# design.net
KiCad netlist of a schematic drawn in Altium Designer
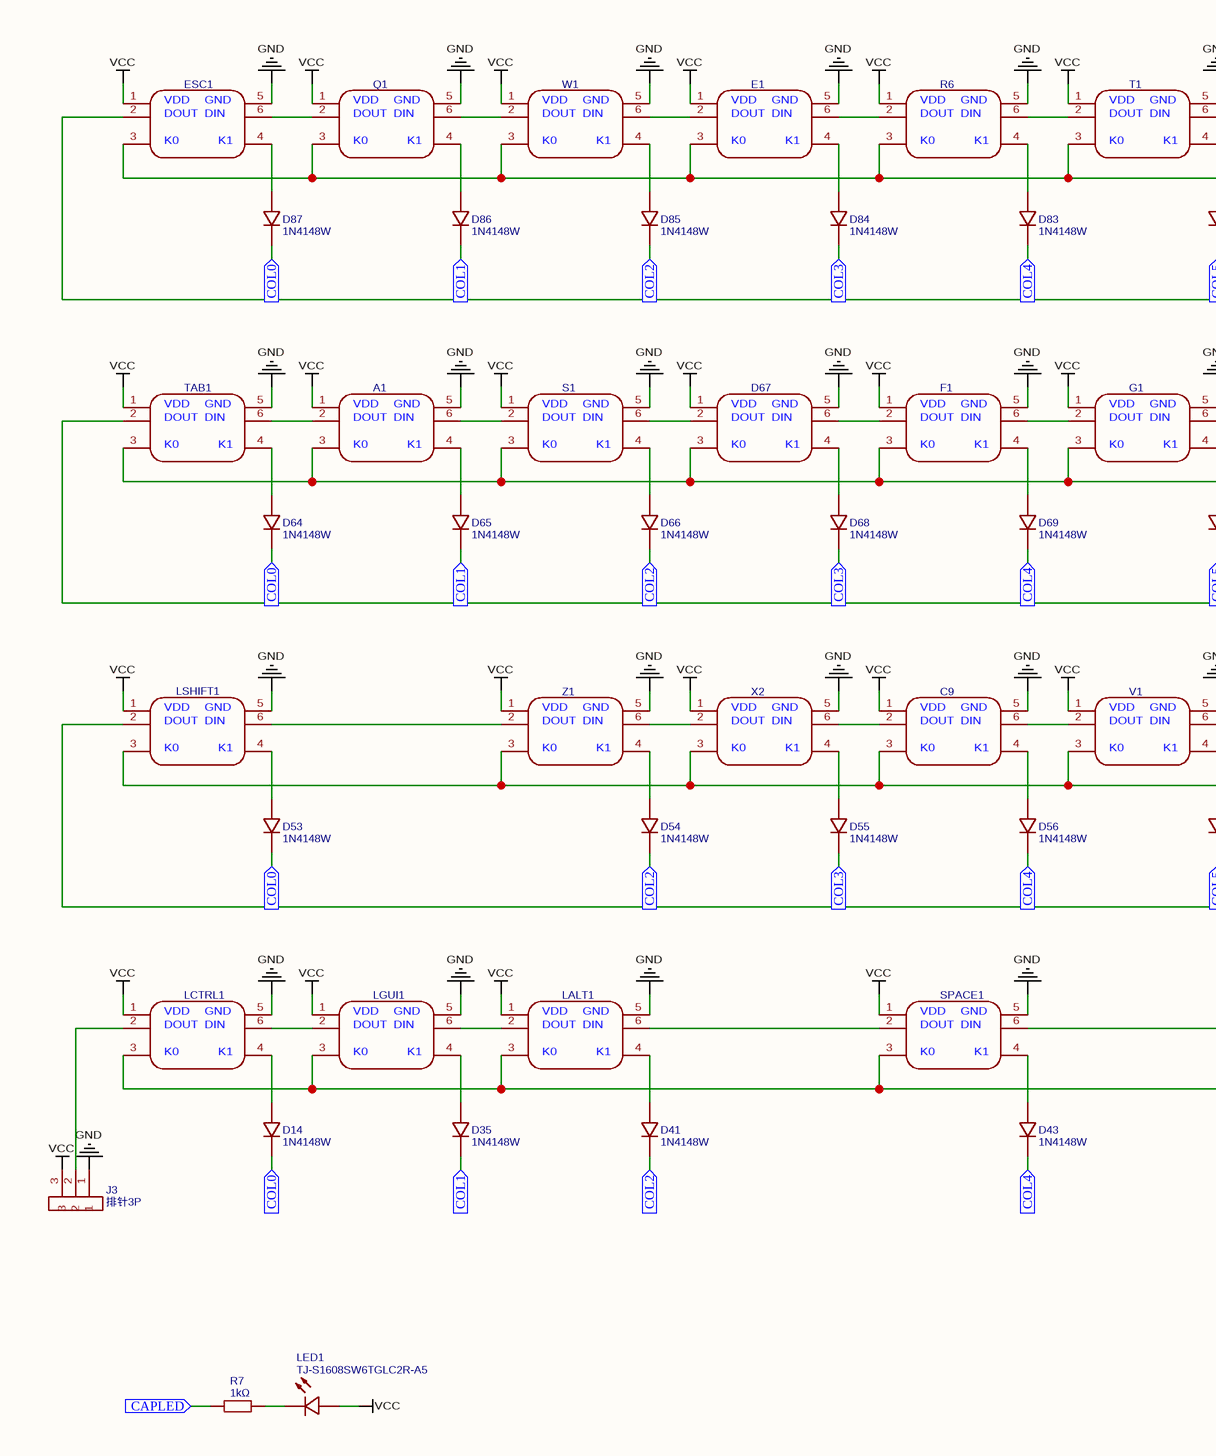
[diagram p0: 键盘矩阵.schdoc, left]
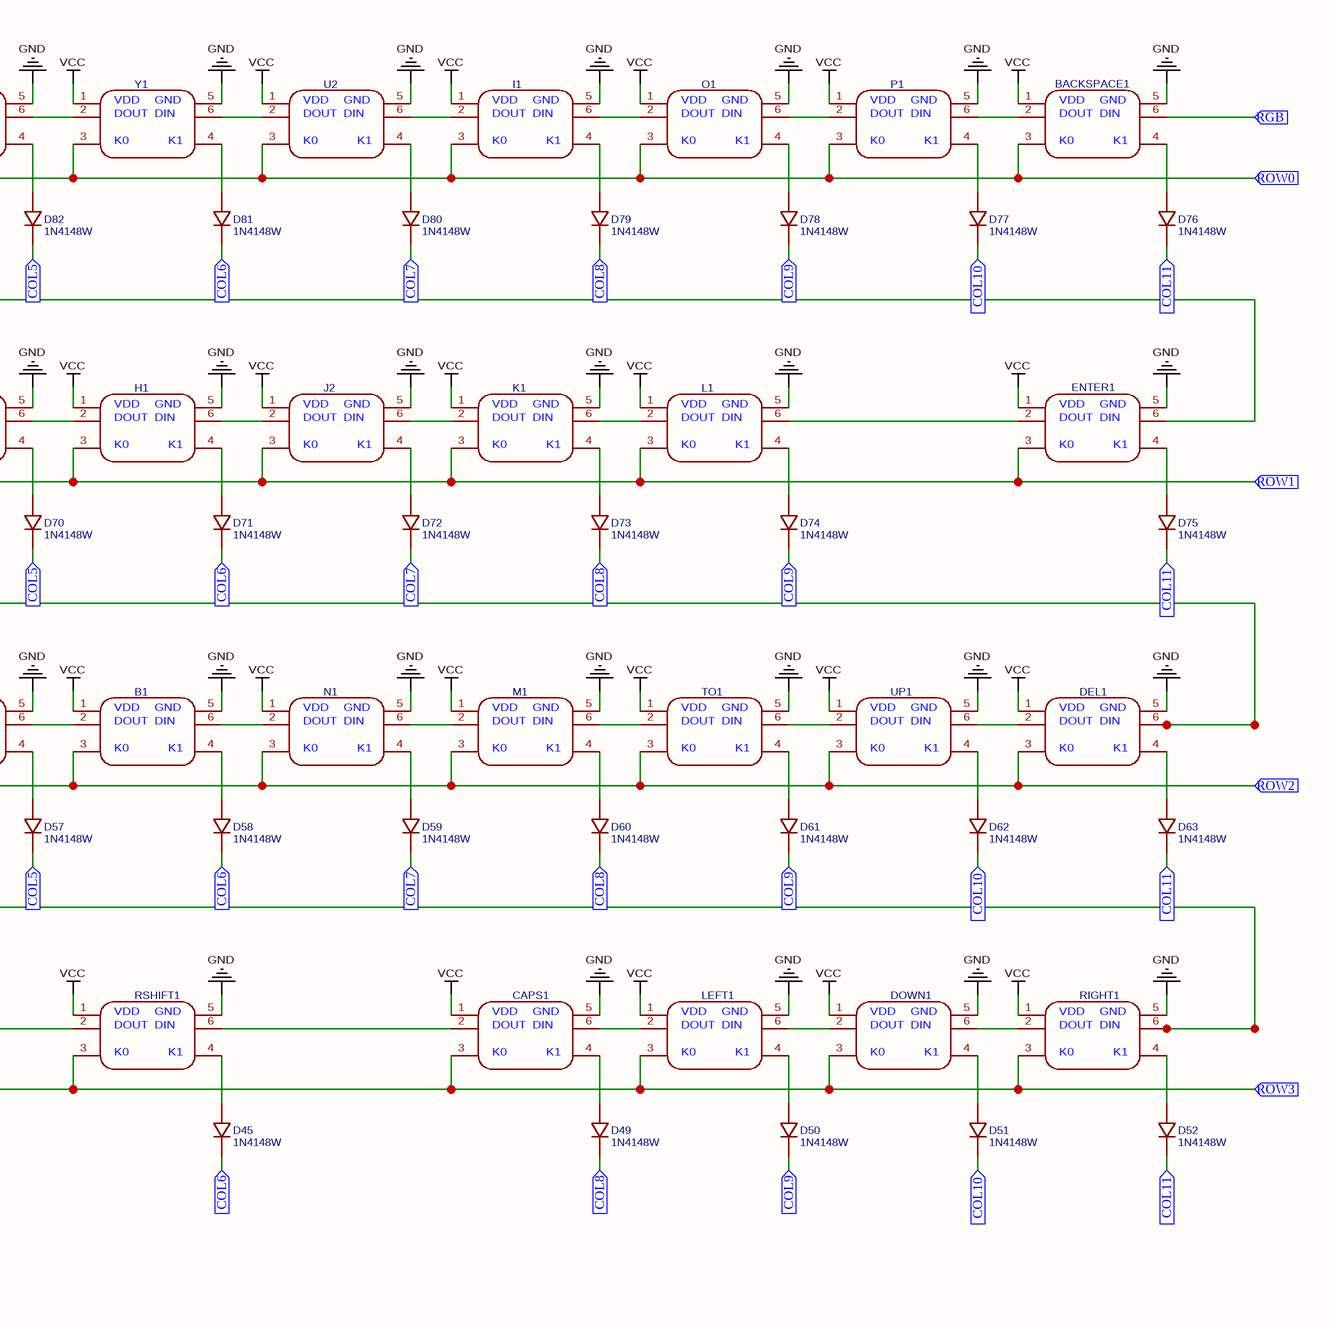
[diagram p1: 键盘矩阵.schdoc, right]

(export (version "E")
  (design (tool "Eeschema 10.0.6"))
  (components
    (comp (ref "A1")
      (value "凯华轴座+3528反贴灯")
      (fields (field (name "CONTRIBUTOR") "LAN_23333"))
      (libsource (lib "altium-import") (part "root_0_凯华轴座+3528反贴灯_"))
    )
    (comp (ref "B1")
      (value "凯华轴座+3528反贴灯")
      (fields (field (name "CONTRIBUTOR") "LAN_23333"))
      (libsource (lib "altium-import") (part "root_0_凯华轴座+3528反贴灯_"))
    )
    (comp (ref "BACKSPACE1")
      (value "凯华轴座+3528反贴灯")
      (fields (field (name "CONTRIBUTOR") "LAN_23333"))
      (libsource (lib "altium-import") (part "root_0_凯华轴座+3528反贴灯_"))
    )
    (comp (ref "C9")
      (value "凯华轴座+3528反贴灯")
      (fields (field (name "CONTRIBUTOR") "LAN_23333"))
      (libsource (lib "altium-import") (part "root_0_凯华轴座+3528反贴灯_"))
    )
    (comp (ref "CAPS1")
      (value "凯华轴座+3528反贴灯")
      (fields (field (name "CONTRIBUTOR") "LAN_23333"))
      (libsource (lib "altium-import") (part "root_0_凯华轴座+3528反贴灯_"))
    )
    (comp (ref "D14")
      (value "1N4148W")
      (fields (field (name "BOM_SUPPLIER PART") "C179717") (field (name "CONTRIBUTOR") "LCSC"))
      (libsource (lib "altium-import") (part "root_1_1N4148W_"))
    )
    (comp (ref "D35")
      (value "1N4148W")
      (fields (field (name "BOM_SUPPLIER PART") "C179717") (field (name "CONTRIBUTOR") "LCSC"))
      (libsource (lib "altium-import") (part "root_1_1N4148W_"))
    )
    (comp (ref "D41")
      (value "1N4148W")
      (fields (field (name "BOM_SUPPLIER PART") "C179717") (field (name "CONTRIBUTOR") "LCSC"))
      (libsource (lib "altium-import") (part "root_1_1N4148W_"))
    )
    (comp (ref "D43")
      (value "1N4148W")
      (fields (field (name "BOM_SUPPLIER PART") "C179717") (field (name "CONTRIBUTOR") "LCSC"))
      (libsource (lib "altium-import") (part "root_1_1N4148W_"))
    )
    (comp (ref "D45")
      (value "1N4148W")
      (fields (field (name "BOM_SUPPLIER PART") "C179717") (field (name "CONTRIBUTOR") "LCSC"))
      (libsource (lib "altium-import") (part "root_1_1N4148W_"))
    )
    (comp (ref "D49")
      (value "1N4148W")
      (fields (field (name "BOM_SUPPLIER PART") "C179717") (field (name "CONTRIBUTOR") "LCSC"))
      (libsource (lib "altium-import") (part "root_1_1N4148W_"))
    )
    (comp (ref "D50")
      (value "1N4148W")
      (fields (field (name "BOM_SUPPLIER PART") "C179717") (field (name "CONTRIBUTOR") "LCSC"))
      (libsource (lib "altium-import") (part "root_1_1N4148W_"))
    )
    (comp (ref "D51")
      (value "1N4148W")
      (fields (field (name "BOM_SUPPLIER PART") "C179717") (field (name "CONTRIBUTOR") "LCSC"))
      (libsource (lib "altium-import") (part "root_1_1N4148W_"))
    )
    (comp (ref "D52")
      (value "1N4148W")
      (fields (field (name "BOM_SUPPLIER PART") "C179717") (field (name "CONTRIBUTOR") "LCSC"))
      (libsource (lib "altium-import") (part "root_1_1N4148W_"))
    )
    (comp (ref "D53")
      (value "1N4148W")
      (fields (field (name "BOM_SUPPLIER PART") "C179717") (field (name "CONTRIBUTOR") "LCSC"))
      (libsource (lib "altium-import") (part "root_1_1N4148W_"))
    )
    (comp (ref "D54")
      (value "1N4148W")
      (fields (field (name "BOM_SUPPLIER PART") "C179717") (field (name "CONTRIBUTOR") "LCSC"))
      (libsource (lib "altium-import") (part "root_1_1N4148W_"))
    )
    (comp (ref "D55")
      (value "1N4148W")
      (fields (field (name "BOM_SUPPLIER PART") "C179717") (field (name "CONTRIBUTOR") "LCSC"))
      (libsource (lib "altium-import") (part "root_1_1N4148W_"))
    )
    (comp (ref "D56")
      (value "1N4148W")
      (fields (field (name "BOM_SUPPLIER PART") "C179717") (field (name "CONTRIBUTOR") "LCSC"))
      (libsource (lib "altium-import") (part "root_1_1N4148W_"))
    )
    (comp (ref "D57")
      (value "1N4148W")
      (fields (field (name "BOM_SUPPLIER PART") "C179717") (field (name "CONTRIBUTOR") "LCSC"))
      (libsource (lib "altium-import") (part "root_1_1N4148W_"))
    )
    (comp (ref "D58")
      (value "1N4148W")
      (fields (field (name "BOM_SUPPLIER PART") "C179717") (field (name "CONTRIBUTOR") "LCSC"))
      (libsource (lib "altium-import") (part "root_1_1N4148W_"))
    )
    (comp (ref "D59")
      (value "1N4148W")
      (fields (field (name "BOM_SUPPLIER PART") "C179717") (field (name "CONTRIBUTOR") "LCSC"))
      (libsource (lib "altium-import") (part "root_1_1N4148W_"))
    )
    (comp (ref "D60")
      (value "1N4148W")
      (fields (field (name "BOM_SUPPLIER PART") "C179717") (field (name "CONTRIBUTOR") "LCSC"))
      (libsource (lib "altium-import") (part "root_1_1N4148W_"))
    )
    (comp (ref "D61")
      (value "1N4148W")
      (fields (field (name "BOM_SUPPLIER PART") "C179717") (field (name "CONTRIBUTOR") "LCSC"))
      (libsource (lib "altium-import") (part "root_1_1N4148W_"))
    )
    (comp (ref "D62")
      (value "1N4148W")
      (fields (field (name "BOM_SUPPLIER PART") "C179717") (field (name "CONTRIBUTOR") "LCSC"))
      (libsource (lib "altium-import") (part "root_1_1N4148W_"))
    )
    (comp (ref "D63")
      (value "1N4148W")
      (fields (field (name "BOM_SUPPLIER PART") "C179717") (field (name "CONTRIBUTOR") "LCSC"))
      (libsource (lib "altium-import") (part "root_1_1N4148W_"))
    )
    (comp (ref "D64")
      (value "1N4148W")
      (fields (field (name "BOM_SUPPLIER PART") "C179717") (field (name "CONTRIBUTOR") "LCSC"))
      (libsource (lib "altium-import") (part "root_1_1N4148W_"))
    )
    (comp (ref "D65")
      (value "1N4148W")
      (fields (field (name "BOM_SUPPLIER PART") "C179717") (field (name "CONTRIBUTOR") "LCSC"))
      (libsource (lib "altium-import") (part "root_1_1N4148W_"))
    )
    (comp (ref "D66")
      (value "1N4148W")
      (fields (field (name "BOM_SUPPLIER PART") "C179717") (field (name "CONTRIBUTOR") "LCSC"))
      (libsource (lib "altium-import") (part "root_1_1N4148W_"))
    )
    (comp (ref "D67")
      (value "凯华轴座+3528反贴灯")
      (fields (field (name "CONTRIBUTOR") "LAN_23333"))
      (libsource (lib "altium-import") (part "root_0_凯华轴座+3528反贴灯_"))
    )
    (comp (ref "D68")
      (value "1N4148W")
      (fields (field (name "BOM_SUPPLIER PART") "C179717") (field (name "CONTRIBUTOR") "LCSC"))
      (libsource (lib "altium-import") (part "root_1_1N4148W_"))
    )
    (comp (ref "D69")
      (value "1N4148W")
      (fields (field (name "BOM_SUPPLIER PART") "C179717") (field (name "CONTRIBUTOR") "LCSC"))
      (libsource (lib "altium-import") (part "root_1_1N4148W_"))
    )
    (comp (ref "D70")
      (value "1N4148W")
      (fields (field (name "BOM_SUPPLIER PART") "C179717") (field (name "CONTRIBUTOR") "LCSC"))
      (libsource (lib "altium-import") (part "root_1_1N4148W_"))
    )
    (comp (ref "D71")
      (value "1N4148W")
      (fields (field (name "BOM_SUPPLIER PART") "C179717") (field (name "CONTRIBUTOR") "LCSC"))
      (libsource (lib "altium-import") (part "root_1_1N4148W_"))
    )
    (comp (ref "D72")
      (value "1N4148W")
      (fields (field (name "BOM_SUPPLIER PART") "C179717") (field (name "CONTRIBUTOR") "LCSC"))
      (libsource (lib "altium-import") (part "root_1_1N4148W_"))
    )
    (comp (ref "D73")
      (value "1N4148W")
      (fields (field (name "BOM_SUPPLIER PART") "C179717") (field (name "CONTRIBUTOR") "LCSC"))
      (libsource (lib "altium-import") (part "root_1_1N4148W_"))
    )
    (comp (ref "D74")
      (value "1N4148W")
      (fields (field (name "BOM_SUPPLIER PART") "C179717") (field (name "CONTRIBUTOR") "LCSC"))
      (libsource (lib "altium-import") (part "root_1_1N4148W_"))
    )
    (comp (ref "D75")
      (value "1N4148W")
      (fields (field (name "BOM_SUPPLIER PART") "C179717") (field (name "CONTRIBUTOR") "LCSC"))
      (libsource (lib "altium-import") (part "root_1_1N4148W_"))
    )
    (comp (ref "D76")
      (value "1N4148W")
      (fields (field (name "BOM_SUPPLIER PART") "C179717") (field (name "CONTRIBUTOR") "LCSC"))
      (libsource (lib "altium-import") (part "root_1_1N4148W_"))
    )
    (comp (ref "D77")
      (value "1N4148W")
      (fields (field (name "BOM_SUPPLIER PART") "C179717") (field (name "CONTRIBUTOR") "LCSC"))
      (libsource (lib "altium-import") (part "root_1_1N4148W_"))
    )
    (comp (ref "D78")
      (value "1N4148W")
      (fields (field (name "BOM_SUPPLIER PART") "C179717") (field (name "CONTRIBUTOR") "LCSC"))
      (libsource (lib "altium-import") (part "root_1_1N4148W_"))
    )
    (comp (ref "D79")
      (value "1N4148W")
      (fields (field (name "BOM_SUPPLIER PART") "C179717") (field (name "CONTRIBUTOR") "LCSC"))
      (libsource (lib "altium-import") (part "root_1_1N4148W_"))
    )
    (comp (ref "D80")
      (value "1N4148W")
      (fields (field (name "BOM_SUPPLIER PART") "C179717") (field (name "CONTRIBUTOR") "LCSC"))
      (libsource (lib "altium-import") (part "root_1_1N4148W_"))
    )
    (comp (ref "D81")
      (value "1N4148W")
      (fields (field (name "BOM_SUPPLIER PART") "C179717") (field (name "CONTRIBUTOR") "LCSC"))
      (libsource (lib "altium-import") (part "root_1_1N4148W_"))
    )
    (comp (ref "D82")
      (value "1N4148W")
      (fields (field (name "BOM_SUPPLIER PART") "C179717") (field (name "CONTRIBUTOR") "LCSC"))
      (libsource (lib "altium-import") (part "root_1_1N4148W_"))
    )
    (comp (ref "D83")
      (value "1N4148W")
      (fields (field (name "BOM_SUPPLIER PART") "C179717") (field (name "CONTRIBUTOR") "LCSC"))
      (libsource (lib "altium-import") (part "root_1_1N4148W_"))
    )
    (comp (ref "D84")
      (value "1N4148W")
      (fields (field (name "BOM_SUPPLIER PART") "C179717") (field (name "CONTRIBUTOR") "LCSC"))
      (libsource (lib "altium-import") (part "root_1_1N4148W_"))
    )
    (comp (ref "D85")
      (value "1N4148W")
      (fields (field (name "BOM_SUPPLIER PART") "C179717") (field (name "CONTRIBUTOR") "LCSC"))
      (libsource (lib "altium-import") (part "root_1_1N4148W_"))
    )
    (comp (ref "D86")
      (value "1N4148W")
      (fields (field (name "BOM_SUPPLIER PART") "C179717") (field (name "CONTRIBUTOR") "LCSC"))
      (libsource (lib "altium-import") (part "root_1_1N4148W_"))
    )
    (comp (ref "D87")
      (value "1N4148W")
      (fields (field (name "BOM_SUPPLIER PART") "C179717") (field (name "CONTRIBUTOR") "LCSC"))
      (libsource (lib "altium-import") (part "root_1_1N4148W_"))
    )
    (comp (ref "DEL1")
      (value "凯华轴座+3528反贴灯")
      (fields (field (name "CONTRIBUTOR") "LAN_23333"))
      (libsource (lib "altium-import") (part "root_0_凯华轴座+3528反贴灯_"))
    )
    (comp (ref "DOWN1")
      (value "凯华轴座+3528反贴灯")
      (fields (field (name "CONTRIBUTOR") "LAN_23333"))
      (libsource (lib "altium-import") (part "root_0_凯华轴座+3528反贴灯_"))
    )
    (comp (ref "E1")
      (value "凯华轴座+3528反贴灯")
      (fields (field (name "CONTRIBUTOR") "LAN_23333"))
      (libsource (lib "altium-import") (part "root_0_凯华轴座+3528反贴灯_"))
    )
    (comp (ref "ENTER1")
      (value "凯华轴座+3528反贴灯")
      (fields (field (name "CONTRIBUTOR") "LAN_23333"))
      (libsource (lib "altium-import") (part "root_0_凯华轴座+3528反贴灯_"))
    )
    (comp (ref "ESC1")
      (value "凯华轴座+3528反贴灯")
      (fields (field (name "CONTRIBUTOR") "LAN_23333"))
      (libsource (lib "altium-import") (part "root_0_凯华轴座+3528反贴灯_"))
    )
    (comp (ref "F1")
      (value "凯华轴座+3528反贴灯")
      (fields (field (name "CONTRIBUTOR") "LAN_23333"))
      (libsource (lib "altium-import") (part "root_0_凯华轴座+3528反贴灯_"))
    )
    (comp (ref "G1")
      (value "凯华轴座+3528反贴灯")
      (fields (field (name "CONTRIBUTOR") "LAN_23333"))
      (libsource (lib "altium-import") (part "root_0_凯华轴座+3528反贴灯_"))
    )
    (comp (ref "H1")
      (value "凯华轴座+3528反贴灯")
      (fields (field (name "CONTRIBUTOR") "LAN_23333"))
      (libsource (lib "altium-import") (part "root_0_凯华轴座+3528反贴灯_"))
    )
    (comp (ref "I1")
      (value "凯华轴座+3528反贴灯")
      (fields (field (name "CONTRIBUTOR") "LAN_23333"))
      (libsource (lib "altium-import") (part "root_0_凯华轴座+3528反贴灯_"))
    )
    (comp (ref "J2")
      (value "凯华轴座+3528反贴灯")
      (fields (field (name "CONTRIBUTOR") "LAN_23333"))
      (libsource (lib "altium-import") (part "root_0_凯华轴座+3528反贴灯_"))
    )
    (comp (ref "J3")
      (value "排针3P")
      (fields (field (name "CONTRIBUTOR") "goodhello"))
      (libsource (lib "altium-import") (part "root_3_排针3P_"))
    )
    (comp (ref "K1")
      (value "凯华轴座+3528反贴灯")
      (fields (field (name "CONTRIBUTOR") "LAN_23333"))
      (libsource (lib "altium-import") (part "root_0_凯华轴座+3528反贴灯_"))
    )
    (comp (ref "L1")
      (value "凯华轴座+3528反贴灯")
      (fields (field (name "CONTRIBUTOR") "LAN_23333"))
      (libsource (lib "altium-import") (part "root_0_凯华轴座+3528反贴灯_"))
    )
    (comp (ref "LALT1")
      (value "凯华轴座+3528反贴灯")
      (fields (field (name "CONTRIBUTOR") "LAN_23333"))
      (libsource (lib "altium-import") (part "root_0_凯华轴座+3528反贴灯_"))
    )
    (comp (ref "LCTRL1")
      (value "凯华轴座+3528反贴灯")
      (fields (field (name "CONTRIBUTOR") "LAN_23333"))
      (libsource (lib "altium-import") (part "root_0_凯华轴座+3528反贴灯_"))
    )
    (comp (ref "LED1")
      (value "TJ-S1608SW6TGLC2R-A5")
      (fields (field (name "BOM_SUPPLIER PART") "C192315") (field (name "CONTRIBUTOR") "LCSC"))
      (libsource (lib "altium-import") (part "root_0_TJ-S1608SW6TGLC2R-A5_"))
    )
    (comp (ref "LEFT1")
      (value "凯华轴座+3528反贴灯")
      (fields (field (name "CONTRIBUTOR") "LAN_23333"))
      (libsource (lib "altium-import") (part "root_0_凯华轴座+3528反贴灯_"))
    )
    (comp (ref "LGUI1")
      (value "凯华轴座+3528反贴灯")
      (fields (field (name "CONTRIBUTOR") "LAN_23333"))
      (libsource (lib "altium-import") (part "root_0_凯华轴座+3528反贴灯_"))
    )
    (comp (ref "LSHIFT1")
      (value "凯华轴座+3528反贴灯")
      (fields (field (name "CONTRIBUTOR") "LAN_23333"))
      (libsource (lib "altium-import") (part "root_0_凯华轴座+3528反贴灯_"))
    )
    (comp (ref "M1")
      (value "凯华轴座+3528反贴灯")
      (fields (field (name "CONTRIBUTOR") "LAN_23333"))
      (libsource (lib "altium-import") (part "root_0_凯华轴座+3528反贴灯_"))
    )
    (comp (ref "N1")
      (value "凯华轴座+3528反贴灯")
      (fields (field (name "CONTRIBUTOR") "LAN_23333"))
      (libsource (lib "altium-import") (part "root_0_凯华轴座+3528反贴灯_"))
    )
    (comp (ref "O1")
      (value "凯华轴座+3528反贴灯")
      (fields (field (name "CONTRIBUTOR") "LAN_23333"))
      (libsource (lib "altium-import") (part "root_0_凯华轴座+3528反贴灯_"))
    )
    (comp (ref "P1")
      (value "凯华轴座+3528反贴灯")
      (fields (field (name "CONTRIBUTOR") "LAN_23333"))
      (libsource (lib "altium-import") (part "root_0_凯华轴座+3528反贴灯_"))
    )
    (comp (ref "Q1")
      (value "凯华轴座+3528反贴灯")
      (fields (field (name "CONTRIBUTOR") "LAN_23333"))
      (libsource (lib "altium-import") (part "root_0_凯华轴座+3528反贴灯_"))
    )
    (comp (ref "R6")
      (value "凯华轴座+3528反贴灯")
      (fields (field (name "CONTRIBUTOR") "LAN_23333"))
      (libsource (lib "altium-import") (part "root_0_凯华轴座+3528反贴灯_"))
    )
    (comp (ref "R7")
      (value "1kΩ")
      (fields
        (field (name "BOM_SUPPLIER PART") "C365394")
        (field (name "BOM_MANUFACTURER PART") "ETCR0603F1K00K9")
        (field (name "CONTRIBUTOR") "LCSC")
      )
      (libsource (lib "altium-import") (part "root_0_1kΩ_"))
    )
    (comp (ref "RIGHT1")
      (value "凯华轴座+3528反贴灯")
      (fields (field (name "CONTRIBUTOR") "LAN_23333"))
      (libsource (lib "altium-import") (part "root_0_凯华轴座+3528反贴灯_"))
    )
    (comp (ref "RSHIFT1")
      (value "凯华轴座+3528反贴灯")
      (fields (field (name "CONTRIBUTOR") "LAN_23333"))
      (libsource (lib "altium-import") (part "root_0_凯华轴座+3528反贴灯_"))
    )
    (comp (ref "S1")
      (value "凯华轴座+3528反贴灯")
      (fields (field (name "CONTRIBUTOR") "LAN_23333"))
      (libsource (lib "altium-import") (part "root_0_凯华轴座+3528反贴灯_"))
    )
    (comp (ref "SPACE1")
      (value "凯华轴座+3528反贴灯")
      (fields (field (name "CONTRIBUTOR") "LAN_23333"))
      (libsource (lib "altium-import") (part "root_0_凯华轴座+3528反贴灯_"))
    )
    (comp (ref "T1")
      (value "凯华轴座+3528反贴灯")
      (fields (field (name "CONTRIBUTOR") "LAN_23333"))
      (libsource (lib "altium-import") (part "root_0_凯华轴座+3528反贴灯_"))
    )
    (comp (ref "TAB1")
      (value "凯华轴座+3528反贴灯")
      (fields (field (name "CONTRIBUTOR") "LAN_23333"))
      (libsource (lib "altium-import") (part "root_0_凯华轴座+3528反贴灯_"))
    )
    (comp (ref "TO1")
      (value "凯华轴座+3528反贴灯")
      (fields (field (name "CONTRIBUTOR") "LAN_23333"))
      (libsource (lib "altium-import") (part "root_0_凯华轴座+3528反贴灯_"))
    )
    (comp (ref "U2")
      (value "凯华轴座+3528反贴灯")
      (fields (field (name "CONTRIBUTOR") "LAN_23333"))
      (libsource (lib "altium-import") (part "root_0_凯华轴座+3528反贴灯_"))
    )
    (comp (ref "UP1")
      (value "凯华轴座+3528反贴灯")
      (fields (field (name "CONTRIBUTOR") "LAN_23333"))
      (libsource (lib "altium-import") (part "root_0_凯华轴座+3528反贴灯_"))
    )
    (comp (ref "V1")
      (value "凯华轴座+3528反贴灯")
      (fields (field (name "CONTRIBUTOR") "LAN_23333"))
      (libsource (lib "altium-import") (part "root_0_凯华轴座+3528反贴灯_"))
    )
    (comp (ref "W1")
      (value "凯华轴座+3528反贴灯")
      (fields (field (name "CONTRIBUTOR") "LAN_23333"))
      (libsource (lib "altium-import") (part "root_0_凯华轴座+3528反贴灯_"))
    )
    (comp (ref "X2")
      (value "凯华轴座+3528反贴灯")
      (fields (field (name "CONTRIBUTOR") "LAN_23333"))
      (libsource (lib "altium-import") (part "root_0_凯华轴座+3528反贴灯_"))
    )
    (comp (ref "Y1")
      (value "凯华轴座+3528反贴灯")
      (fields (field (name "CONTRIBUTOR") "LAN_23333"))
      (libsource (lib "altium-import") (part "root_0_凯华轴座+3528反贴灯_"))
    )
    (comp (ref "Z1")
      (value "凯华轴座+3528反贴灯")
      (fields (field (name "CONTRIBUTOR") "LAN_23333"))
      (libsource (lib "altium-import") (part "root_0_凯华轴座+3528反贴灯_"))
    )
  )
  (nets
    (net (code "1") (name "/CAPLED") (class "Default")
      (node (ref "R7") (pin "1") (pinfunction "1_1") (pintype "passive"))
    )
    (net (code "2") (name "/COL0") (class "Default")
      (node (ref "D14") (pin "1") (pinfunction "K_1") (pintype "passive"))
      (node (ref "D53") (pin "1") (pinfunction "K_1") (pintype "passive"))
      (node (ref "D64") (pin "1") (pinfunction "K_1") (pintype "passive"))
      (node (ref "D87") (pin "1") (pinfunction "K_1") (pintype "passive"))
    )
    (net (code "3") (name "/COL1") (class "Default")
      (node (ref "D35") (pin "1") (pinfunction "K_1") (pintype "passive"))
      (node (ref "D65") (pin "1") (pinfunction "K_1") (pintype "passive"))
      (node (ref "D86") (pin "1") (pinfunction "K_1") (pintype "passive"))
    )
    (net (code "4") (name "/COL2") (class "Default")
      (node (ref "D41") (pin "1") (pinfunction "K_1") (pintype "passive"))
      (node (ref "D54") (pin "1") (pinfunction "K_1") (pintype "passive"))
      (node (ref "D66") (pin "1") (pinfunction "K_1") (pintype "passive"))
      (node (ref "D85") (pin "1") (pinfunction "K_1") (pintype "passive"))
    )
    (net (code "5") (name "/COL3") (class "Default")
      (node (ref "D55") (pin "1") (pinfunction "K_1") (pintype "passive"))
      (node (ref "D68") (pin "1") (pinfunction "K_1") (pintype "passive"))
      (node (ref "D84") (pin "1") (pinfunction "K_1") (pintype "passive"))
    )
    (net (code "6") (name "/COL4") (class "Default")
      (node (ref "D43") (pin "1") (pinfunction "K_1") (pintype "passive"))
      (node (ref "D56") (pin "1") (pinfunction "K_1") (pintype "passive"))
      (node (ref "D69") (pin "1") (pinfunction "K_1") (pintype "passive"))
      (node (ref "D83") (pin "1") (pinfunction "K_1") (pintype "passive"))
    )
    (net (code "7") (name "/COL5") (class "Default")
      (node (ref "D57") (pin "1") (pinfunction "K_1") (pintype "passive"))
      (node (ref "D70") (pin "1") (pinfunction "K_1") (pintype "passive"))
      (node (ref "D82") (pin "1") (pinfunction "K_1") (pintype "passive"))
    )
    (net (code "8") (name "/COL6") (class "Default")
      (node (ref "D45") (pin "1") (pinfunction "K_1") (pintype "passive"))
      (node (ref "D58") (pin "1") (pinfunction "K_1") (pintype "passive"))
      (node (ref "D71") (pin "1") (pinfunction "K_1") (pintype "passive"))
      (node (ref "D81") (pin "1") (pinfunction "K_1") (pintype "passive"))
    )
    (net (code "9") (name "/COL7") (class "Default")
      (node (ref "D59") (pin "1") (pinfunction "K_1") (pintype "passive"))
      (node (ref "D72") (pin "1") (pinfunction "K_1") (pintype "passive"))
      (node (ref "D80") (pin "1") (pinfunction "K_1") (pintype "passive"))
    )
    (net (code "10") (name "/COL8") (class "Default")
      (node (ref "D49") (pin "1") (pinfunction "K_1") (pintype "passive"))
      (node (ref "D60") (pin "1") (pinfunction "K_1") (pintype "passive"))
      (node (ref "D73") (pin "1") (pinfunction "K_1") (pintype "passive"))
      (node (ref "D79") (pin "1") (pinfunction "K_1") (pintype "passive"))
    )
    (net (code "11") (name "/COL9") (class "Default")
      (node (ref "D50") (pin "1") (pinfunction "K_1") (pintype "passive"))
      (node (ref "D61") (pin "1") (pinfunction "K_1") (pintype "passive"))
      (node (ref "D74") (pin "1") (pinfunction "K_1") (pintype "passive"))
      (node (ref "D78") (pin "1") (pinfunction "K_1") (pintype "passive"))
    )
    (net (code "12") (name "/COL10") (class "Default")
      (node (ref "D51") (pin "1") (pinfunction "K_1") (pintype "passive"))
      (node (ref "D62") (pin "1") (pinfunction "K_1") (pintype "passive"))
      (node (ref "D77") (pin "1") (pinfunction "K_1") (pintype "passive"))
    )
    (net (code "13") (name "/COL11") (class "Default")
      (node (ref "D52") (pin "1") (pinfunction "K_1") (pintype "passive"))
      (node (ref "D63") (pin "1") (pinfunction "K_1") (pintype "passive"))
      (node (ref "D75") (pin "1") (pinfunction "K_1") (pintype "passive"))
      (node (ref "D76") (pin "1") (pinfunction "K_1") (pintype "passive"))
    )
    (net (code "14") (name "/RGB") (class "Default")
      (node (ref "BACKSPACE1") (pin "6") (pinfunction "6_6") (pintype "passive"))
    )
    (net (code "15") (name "/ROW0") (class "Default")
      (node (ref "BACKSPACE1") (pin "3") (pinfunction "3_3") (pintype "passive"))
      (node (ref "E1") (pin "3") (pinfunction "3_3") (pintype "passive"))
      (node (ref "ESC1") (pin "3") (pinfunction "3_3") (pintype "passive"))
      (node (ref "I1") (pin "3") (pinfunction "3_3") (pintype "passive"))
      (node (ref "O1") (pin "3") (pinfunction "3_3") (pintype "passive"))
      (node (ref "P1") (pin "3") (pinfunction "3_3") (pintype "passive"))
      (node (ref "Q1") (pin "3") (pinfunction "3_3") (pintype "passive"))
      (node (ref "R6") (pin "3") (pinfunction "3_3") (pintype "passive"))
      (node (ref "T1") (pin "3") (pinfunction "3_3") (pintype "passive"))
      (node (ref "U2") (pin "3") (pinfunction "3_3") (pintype "passive"))
      (node (ref "W1") (pin "3") (pinfunction "3_3") (pintype "passive"))
      (node (ref "Y1") (pin "3") (pinfunction "3_3") (pintype "passive"))
    )
    (net (code "16") (name "/ROW1") (class "Default")
      (node (ref "A1") (pin "3") (pinfunction "3_3") (pintype "passive"))
      (node (ref "D67") (pin "3") (pinfunction "3_3") (pintype "passive"))
      (node (ref "ENTER1") (pin "3") (pinfunction "3_3") (pintype "passive"))
      (node (ref "F1") (pin "3") (pinfunction "3_3") (pintype "passive"))
      (node (ref "G1") (pin "3") (pinfunction "3_3") (pintype "passive"))
      (node (ref "H1") (pin "3") (pinfunction "3_3") (pintype "passive"))
      (node (ref "J2") (pin "3") (pinfunction "3_3") (pintype "passive"))
      (node (ref "K1") (pin "3") (pinfunction "3_3") (pintype "passive"))
      (node (ref "L1") (pin "3") (pinfunction "3_3") (pintype "passive"))
      (node (ref "S1") (pin "3") (pinfunction "3_3") (pintype "passive"))
      (node (ref "TAB1") (pin "3") (pinfunction "3_3") (pintype "passive"))
    )
    (net (code "17") (name "/ROW2") (class "Default")
      (node (ref "B1") (pin "3") (pinfunction "3_3") (pintype "passive"))
      (node (ref "C9") (pin "3") (pinfunction "3_3") (pintype "passive"))
      (node (ref "DEL1") (pin "3") (pinfunction "3_3") (pintype "passive"))
      (node (ref "LSHIFT1") (pin "3") (pinfunction "3_3") (pintype "passive"))
      (node (ref "M1") (pin "3") (pinfunction "3_3") (pintype "passive"))
      (node (ref "N1") (pin "3") (pinfunction "3_3") (pintype "passive"))
      (node (ref "TO1") (pin "3") (pinfunction "3_3") (pintype "passive"))
      (node (ref "UP1") (pin "3") (pinfunction "3_3") (pintype "passive"))
      (node (ref "V1") (pin "3") (pinfunction "3_3") (pintype "passive"))
      (node (ref "X2") (pin "3") (pinfunction "3_3") (pintype "passive"))
      (node (ref "Z1") (pin "3") (pinfunction "3_3") (pintype "passive"))
    )
    (net (code "18") (name "/ROW3") (class "Default")
      (node (ref "CAPS1") (pin "3") (pinfunction "3_3") (pintype "passive"))
      (node (ref "DOWN1") (pin "3") (pinfunction "3_3") (pintype "passive"))
      (node (ref "LALT1") (pin "3") (pinfunction "3_3") (pintype "passive"))
      (node (ref "LCTRL1") (pin "3") (pinfunction "3_3") (pintype "passive"))
      (node (ref "LEFT1") (pin "3") (pinfunction "3_3") (pintype "passive"))
      (node (ref "LGUI1") (pin "3") (pinfunction "3_3") (pintype "passive"))
      (node (ref "RIGHT1") (pin "3") (pinfunction "3_3") (pintype "passive"))
      (node (ref "RSHIFT1") (pin "3") (pinfunction "3_3") (pintype "passive"))
      (node (ref "SPACE1") (pin "3") (pinfunction "3_3") (pintype "passive"))
    )
    (net (code "19") (name "GND") (class "Default")
      (node (ref "A1") (pin "5") (pinfunction "5_5") (pintype "passive"))
      (node (ref "B1") (pin "5") (pinfunction "5_5") (pintype "passive"))
      (node (ref "BACKSPACE1") (pin "5") (pinfunction "5_5") (pintype "passive"))
      (node (ref "C9") (pin "5") (pinfunction "5_5") (pintype "passive"))
      (node (ref "CAPS1") (pin "5") (pinfunction "5_5") (pintype "passive"))
      (node (ref "D67") (pin "5") (pinfunction "5_5") (pintype "passive"))
      (node (ref "DEL1") (pin "5") (pinfunction "5_5") (pintype "passive"))
      (node (ref "DOWN1") (pin "5") (pinfunction "5_5") (pintype "passive"))
      (node (ref "E1") (pin "5") (pinfunction "5_5") (pintype "passive"))
      (node (ref "ENTER1") (pin "5") (pinfunction "5_5") (pintype "passive"))
      (node (ref "ESC1") (pin "5") (pinfunction "5_5") (pintype "passive"))
      (node (ref "F1") (pin "5") (pinfunction "5_5") (pintype "passive"))
      (node (ref "G1") (pin "5") (pinfunction "5_5") (pintype "passive"))
      (node (ref "H1") (pin "5") (pinfunction "5_5") (pintype "passive"))
      (node (ref "I1") (pin "5") (pinfunction "5_5") (pintype "passive"))
      (node (ref "J2") (pin "5") (pinfunction "5_5") (pintype "passive"))
      (node (ref "J3") (pin "1") (pinfunction "1_1") (pintype "passive"))
      (node (ref "K1") (pin "5") (pinfunction "5_5") (pintype "passive"))
      (node (ref "L1") (pin "5") (pinfunction "5_5") (pintype "passive"))
      (node (ref "LALT1") (pin "5") (pinfunction "5_5") (pintype "passive"))
      (node (ref "LCTRL1") (pin "5") (pinfunction "5_5") (pintype "passive"))
      (node (ref "LEFT1") (pin "5") (pinfunction "5_5") (pintype "passive"))
      (node (ref "LGUI1") (pin "5") (pinfunction "5_5") (pintype "passive"))
      (node (ref "LSHIFT1") (pin "5") (pinfunction "5_5") (pintype "passive"))
      (node (ref "M1") (pin "5") (pinfunction "5_5") (pintype "passive"))
      (node (ref "N1") (pin "5") (pinfunction "5_5") (pintype "passive"))
      (node (ref "O1") (pin "5") (pinfunction "5_5") (pintype "passive"))
      (node (ref "P1") (pin "5") (pinfunction "5_5") (pintype "passive"))
      (node (ref "Q1") (pin "5") (pinfunction "5_5") (pintype "passive"))
      (node (ref "R6") (pin "5") (pinfunction "5_5") (pintype "passive"))
      (node (ref "RIGHT1") (pin "5") (pinfunction "5_5") (pintype "passive"))
      (node (ref "RSHIFT1") (pin "5") (pinfunction "5_5") (pintype "passive"))
      (node (ref "S1") (pin "5") (pinfunction "5_5") (pintype "passive"))
      (node (ref "SPACE1") (pin "5") (pinfunction "5_5") (pintype "passive"))
      (node (ref "T1") (pin "5") (pinfunction "5_5") (pintype "passive"))
      (node (ref "TAB1") (pin "5") (pinfunction "5_5") (pintype "passive"))
      (node (ref "TO1") (pin "5") (pinfunction "5_5") (pintype "passive"))
      (node (ref "U2") (pin "5") (pinfunction "5_5") (pintype "passive"))
      (node (ref "UP1") (pin "5") (pinfunction "5_5") (pintype "passive"))
      (node (ref "V1") (pin "5") (pinfunction "5_5") (pintype "passive"))
      (node (ref "W1") (pin "5") (pinfunction "5_5") (pintype "passive"))
      (node (ref "X2") (pin "5") (pinfunction "5_5") (pintype "passive"))
      (node (ref "Y1") (pin "5") (pinfunction "5_5") (pintype "passive"))
      (node (ref "Z1") (pin "5") (pinfunction "5_5") (pintype "passive"))
    )
    (net (code "20") (name "Net-(A1-Pad2)") (class "Default")
      (node (ref "A1") (pin "2") (pinfunction "2_2") (pintype "passive"))
      (node (ref "TAB1") (pin "6") (pinfunction "6_6") (pintype "passive"))
    )
    (net (code "21") (name "Net-(A1-Pad6)") (class "Default")
      (node (ref "A1") (pin "6") (pinfunction "6_6") (pintype "passive"))
      (node (ref "S1") (pin "2") (pinfunction "2_2") (pintype "passive"))
    )
    (net (code "22") (name "Net-(B1-Pad2)") (class "Default")
      (node (ref "B1") (pin "2") (pinfunction "2_2") (pintype "passive"))
      (node (ref "V1") (pin "6") (pinfunction "6_6") (pintype "passive"))
    )
    (net (code "23") (name "Net-(B1-Pad6)") (class "Default")
      (node (ref "B1") (pin "6") (pinfunction "6_6") (pintype "passive"))
      (node (ref "N1") (pin "2") (pinfunction "2_2") (pintype "passive"))
    )
    (net (code "24") (name "Net-(BACKSPACE1-Pad2)") (class "Default")
      (node (ref "BACKSPACE1") (pin "2") (pinfunction "2_2") (pintype "passive"))
      (node (ref "P1") (pin "6") (pinfunction "6_6") (pintype "passive"))
    )
    (net (code "25") (name "Net-(C9-Pad2)") (class "Default")
      (node (ref "C9") (pin "2") (pinfunction "2_2") (pintype "passive"))
      (node (ref "X2") (pin "6") (pinfunction "6_6") (pintype "passive"))
    )
    (net (code "26") (name "Net-(C9-Pad6)") (class "Default")
      (node (ref "C9") (pin "6") (pinfunction "6_6") (pintype "passive"))
      (node (ref "V1") (pin "2") (pinfunction "2_2") (pintype "passive"))
    )
    (net (code "27") (name "Net-(CAPS1-Pad2)") (class "Default")
      (node (ref "CAPS1") (pin "2") (pinfunction "2_2") (pintype "passive"))
      (node (ref "RSHIFT1") (pin "6") (pinfunction "6_6") (pintype "passive"))
    )
    (net (code "28") (name "Net-(CAPS1-Pad6)") (class "Default")
      (node (ref "CAPS1") (pin "6") (pinfunction "6_6") (pintype "passive"))
      (node (ref "LEFT1") (pin "2") (pinfunction "2_2") (pintype "passive"))
    )
    (net (code "29") (name "Net-(D14-A)") (class "Default")
      (node (ref "D14") (pin "2") (pinfunction "A_2") (pintype "passive"))
      (node (ref "LCTRL1") (pin "4") (pinfunction "4_4") (pintype "passive"))
    )
    (net (code "30") (name "Net-(D35-A)") (class "Default")
      (node (ref "D35") (pin "2") (pinfunction "A_2") (pintype "passive"))
      (node (ref "LGUI1") (pin "4") (pinfunction "4_4") (pintype "passive"))
    )
    (net (code "31") (name "Net-(D41-A)") (class "Default")
      (node (ref "D41") (pin "2") (pinfunction "A_2") (pintype "passive"))
      (node (ref "LALT1") (pin "4") (pinfunction "4_4") (pintype "passive"))
    )
    (net (code "32") (name "Net-(D43-A)") (class "Default")
      (node (ref "D43") (pin "2") (pinfunction "A_2") (pintype "passive"))
      (node (ref "SPACE1") (pin "4") (pinfunction "4_4") (pintype "passive"))
    )
    (net (code "33") (name "Net-(D45-A)") (class "Default")
      (node (ref "D45") (pin "2") (pinfunction "A_2") (pintype "passive"))
      (node (ref "RSHIFT1") (pin "4") (pinfunction "4_4") (pintype "passive"))
    )
    (net (code "34") (name "Net-(D49-A)") (class "Default")
      (node (ref "CAPS1") (pin "4") (pinfunction "4_4") (pintype "passive"))
      (node (ref "D49") (pin "2") (pinfunction "A_2") (pintype "passive"))
    )
    (net (code "35") (name "Net-(D50-A)") (class "Default")
      (node (ref "D50") (pin "2") (pinfunction "A_2") (pintype "passive"))
      (node (ref "LEFT1") (pin "4") (pinfunction "4_4") (pintype "passive"))
    )
    (net (code "36") (name "Net-(D51-A)") (class "Default")
      (node (ref "D51") (pin "2") (pinfunction "A_2") (pintype "passive"))
      (node (ref "DOWN1") (pin "4") (pinfunction "4_4") (pintype "passive"))
    )
    (net (code "37") (name "Net-(D52-A)") (class "Default")
      (node (ref "D52") (pin "2") (pinfunction "A_2") (pintype "passive"))
      (node (ref "RIGHT1") (pin "4") (pinfunction "4_4") (pintype "passive"))
    )
    (net (code "38") (name "Net-(D53-A)") (class "Default")
      (node (ref "D53") (pin "2") (pinfunction "A_2") (pintype "passive"))
      (node (ref "LSHIFT1") (pin "4") (pinfunction "4_4") (pintype "passive"))
    )
    (net (code "39") (name "Net-(D54-A)") (class "Default")
      (node (ref "D54") (pin "2") (pinfunction "A_2") (pintype "passive"))
      (node (ref "Z1") (pin "4") (pinfunction "4_4") (pintype "passive"))
    )
    (net (code "40") (name "Net-(D55-A)") (class "Default")
      (node (ref "D55") (pin "2") (pinfunction "A_2") (pintype "passive"))
      (node (ref "X2") (pin "4") (pinfunction "4_4") (pintype "passive"))
    )
    (net (code "41") (name "Net-(D56-A)") (class "Default")
      (node (ref "C9") (pin "4") (pinfunction "4_4") (pintype "passive"))
      (node (ref "D56") (pin "2") (pinfunction "A_2") (pintype "passive"))
    )
    (net (code "42") (name "Net-(D57-A)") (class "Default")
      (node (ref "D57") (pin "2") (pinfunction "A_2") (pintype "passive"))
      (node (ref "V1") (pin "4") (pinfunction "4_4") (pintype "passive"))
    )
    (net (code "43") (name "Net-(D58-A)") (class "Default")
      (node (ref "B1") (pin "4") (pinfunction "4_4") (pintype "passive"))
      (node (ref "D58") (pin "2") (pinfunction "A_2") (pintype "passive"))
    )
    (net (code "44") (name "Net-(D59-A)") (class "Default")
      (node (ref "D59") (pin "2") (pinfunction "A_2") (pintype "passive"))
      (node (ref "N1") (pin "4") (pinfunction "4_4") (pintype "passive"))
    )
    (net (code "45") (name "Net-(D60-A)") (class "Default")
      (node (ref "D60") (pin "2") (pinfunction "A_2") (pintype "passive"))
      (node (ref "M1") (pin "4") (pinfunction "4_4") (pintype "passive"))
    )
    (net (code "46") (name "Net-(D61-A)") (class "Default")
      (node (ref "D61") (pin "2") (pinfunction "A_2") (pintype "passive"))
      (node (ref "TO1") (pin "4") (pinfunction "4_4") (pintype "passive"))
    )
    (net (code "47") (name "Net-(D62-A)") (class "Default")
      (node (ref "D62") (pin "2") (pinfunction "A_2") (pintype "passive"))
      (node (ref "UP1") (pin "4") (pinfunction "4_4") (pintype "passive"))
    )
    (net (code "48") (name "Net-(D63-A)") (class "Default")
      (node (ref "D63") (pin "2") (pinfunction "A_2") (pintype "passive"))
      (node (ref "DEL1") (pin "4") (pinfunction "4_4") (pintype "passive"))
    )
    (net (code "49") (name "Net-(D64-A)") (class "Default")
      (node (ref "D64") (pin "2") (pinfunction "A_2") (pintype "passive"))
      (node (ref "TAB1") (pin "4") (pinfunction "4_4") (pintype "passive"))
    )
    (net (code "50") (name "Net-(D65-A)") (class "Default")
      (node (ref "A1") (pin "4") (pinfunction "4_4") (pintype "passive"))
      (node (ref "D65") (pin "2") (pinfunction "A_2") (pintype "passive"))
    )
    (net (code "51") (name "Net-(D66-A)") (class "Default")
      (node (ref "D66") (pin "2") (pinfunction "A_2") (pintype "passive"))
      (node (ref "S1") (pin "4") (pinfunction "4_4") (pintype "passive"))
    )
    (net (code "52") (name "Net-(D67-Pad2)") (class "Default")
      (node (ref "D67") (pin "2") (pinfunction "2_2") (pintype "passive"))
      (node (ref "S1") (pin "6") (pinfunction "6_6") (pintype "passive"))
    )
    (net (code "53") (name "Net-(D67-Pad6)") (class "Default")
      (node (ref "D67") (pin "6") (pinfunction "6_6") (pintype "passive"))
      (node (ref "F1") (pin "2") (pinfunction "2_2") (pintype "passive"))
    )
    (net (code "54") (name "Net-(D68-A)") (class "Default")
      (node (ref "D67") (pin "4") (pinfunction "4_4") (pintype "passive"))
      (node (ref "D68") (pin "2") (pinfunction "A_2") (pintype "passive"))
    )
    (net (code "55") (name "Net-(D69-A)") (class "Default")
      (node (ref "D69") (pin "2") (pinfunction "A_2") (pintype "passive"))
      (node (ref "F1") (pin "4") (pinfunction "4_4") (pintype "passive"))
    )
    (net (code "56") (name "Net-(D70-A)") (class "Default")
      (node (ref "D70") (pin "2") (pinfunction "A_2") (pintype "passive"))
      (node (ref "G1") (pin "4") (pinfunction "4_4") (pintype "passive"))
    )
    (net (code "57") (name "Net-(D71-A)") (class "Default")
      (node (ref "D71") (pin "2") (pinfunction "A_2") (pintype "passive"))
      (node (ref "H1") (pin "4") (pinfunction "4_4") (pintype "passive"))
    )
    (net (code "58") (name "Net-(D72-A)") (class "Default")
      (node (ref "D72") (pin "2") (pinfunction "A_2") (pintype "passive"))
      (node (ref "J2") (pin "4") (pinfunction "4_4") (pintype "passive"))
    )
    (net (code "59") (name "Net-(D73-A)") (class "Default")
      (node (ref "D73") (pin "2") (pinfunction "A_2") (pintype "passive"))
      (node (ref "K1") (pin "4") (pinfunction "4_4") (pintype "passive"))
    )
    (net (code "60") (name "Net-(D74-A)") (class "Default")
      (node (ref "D74") (pin "2") (pinfunction "A_2") (pintype "passive"))
      (node (ref "L1") (pin "4") (pinfunction "4_4") (pintype "passive"))
    )
    (net (code "61") (name "Net-(D75-A)") (class "Default")
      (node (ref "D75") (pin "2") (pinfunction "A_2") (pintype "passive"))
      (node (ref "ENTER1") (pin "4") (pinfunction "4_4") (pintype "passive"))
    )
    (net (code "62") (name "Net-(D76-A)") (class "Default")
      (node (ref "BACKSPACE1") (pin "4") (pinfunction "4_4") (pintype "passive"))
      (node (ref "D76") (pin "2") (pinfunction "A_2") (pintype "passive"))
    )
    (net (code "63") (name "Net-(D77-A)") (class "Default")
      (node (ref "D77") (pin "2") (pinfunction "A_2") (pintype "passive"))
      (node (ref "P1") (pin "4") (pinfunction "4_4") (pintype "passive"))
    )
    (net (code "64") (name "Net-(D78-A)") (class "Default")
      (node (ref "D78") (pin "2") (pinfunction "A_2") (pintype "passive"))
      (node (ref "O1") (pin "4") (pinfunction "4_4") (pintype "passive"))
    )
    (net (code "65") (name "Net-(D79-A)") (class "Default")
      (node (ref "D79") (pin "2") (pinfunction "A_2") (pintype "passive"))
      (node (ref "I1") (pin "4") (pinfunction "4_4") (pintype "passive"))
    )
    (net (code "66") (name "Net-(D80-A)") (class "Default")
      (node (ref "D80") (pin "2") (pinfunction "A_2") (pintype "passive"))
      (node (ref "U2") (pin "4") (pinfunction "4_4") (pintype "passive"))
    )
    (net (code "67") (name "Net-(D81-A)") (class "Default")
      (node (ref "D81") (pin "2") (pinfunction "A_2") (pintype "passive"))
      (node (ref "Y1") (pin "4") (pinfunction "4_4") (pintype "passive"))
    )
    (net (code "68") (name "Net-(D82-A)") (class "Default")
      (node (ref "D82") (pin "2") (pinfunction "A_2") (pintype "passive"))
      (node (ref "T1") (pin "4") (pinfunction "4_4") (pintype "passive"))
    )
    (net (code "69") (name "Net-(D83-A)") (class "Default")
      (node (ref "D83") (pin "2") (pinfunction "A_2") (pintype "passive"))
      (node (ref "R6") (pin "4") (pinfunction "4_4") (pintype "passive"))
    )
    (net (code "70") (name "Net-(D84-A)") (class "Default")
      (node (ref "D84") (pin "2") (pinfunction "A_2") (pintype "passive"))
      (node (ref "E1") (pin "4") (pinfunction "4_4") (pintype "passive"))
    )
    (net (code "71") (name "Net-(D85-A)") (class "Default")
      (node (ref "D85") (pin "2") (pinfunction "A_2") (pintype "passive"))
      (node (ref "W1") (pin "4") (pinfunction "4_4") (pintype "passive"))
    )
    (net (code "72") (name "Net-(D86-A)") (class "Default")
      (node (ref "D86") (pin "2") (pinfunction "A_2") (pintype "passive"))
      (node (ref "Q1") (pin "4") (pinfunction "4_4") (pintype "passive"))
    )
    (net (code "73") (name "Net-(D87-A)") (class "Default")
      (node (ref "D87") (pin "2") (pinfunction "A_2") (pintype "passive"))
      (node (ref "ESC1") (pin "4") (pinfunction "4_4") (pintype "passive"))
    )
    (net (code "74") (name "Net-(DEL1-Pad2)") (class "Default")
      (node (ref "DEL1") (pin "2") (pinfunction "2_2") (pintype "passive"))
      (node (ref "UP1") (pin "6") (pinfunction "6_6") (pintype "passive"))
    )
    (net (code "75") (name "Net-(DEL1-Pad6)") (class "Default")
      (node (ref "DEL1") (pin "6") (pinfunction "6_6") (pintype "passive"))
      (node (ref "TAB1") (pin "2") (pinfunction "2_2") (pintype "passive"))
    )
    (net (code "76") (name "Net-(DOWN1-Pad2)") (class "Default")
      (node (ref "DOWN1") (pin "2") (pinfunction "2_2") (pintype "passive"))
      (node (ref "LEFT1") (pin "6") (pinfunction "6_6") (pintype "passive"))
    )
    (net (code "77") (name "Net-(DOWN1-Pad6)") (class "Default")
      (node (ref "DOWN1") (pin "6") (pinfunction "6_6") (pintype "passive"))
      (node (ref "RIGHT1") (pin "2") (pinfunction "2_2") (pintype "passive"))
    )
    (net (code "78") (name "Net-(E1-Pad2)") (class "Default")
      (node (ref "E1") (pin "2") (pinfunction "2_2") (pintype "passive"))
      (node (ref "W1") (pin "6") (pinfunction "6_6") (pintype "passive"))
    )
    (net (code "79") (name "Net-(E1-Pad6)") (class "Default")
      (node (ref "E1") (pin "6") (pinfunction "6_6") (pintype "passive"))
      (node (ref "R6") (pin "2") (pinfunction "2_2") (pintype "passive"))
    )
    (net (code "80") (name "Net-(ENTER1-Pad2)") (class "Default")
      (node (ref "ENTER1") (pin "2") (pinfunction "2_2") (pintype "passive"))
      (node (ref "L1") (pin "6") (pinfunction "6_6") (pintype "passive"))
    )
    (net (code "81") (name "Net-(ENTER1-Pad6)") (class "Default")
      (node (ref "ENTER1") (pin "6") (pinfunction "6_6") (pintype "passive"))
      (node (ref "ESC1") (pin "2") (pinfunction "2_2") (pintype "passive"))
    )
    (net (code "82") (name "Net-(ESC1-Pad6)") (class "Default")
      (node (ref "ESC1") (pin "6") (pinfunction "6_6") (pintype "passive"))
      (node (ref "Q1") (pin "2") (pinfunction "2_2") (pintype "passive"))
    )
    (net (code "83") (name "Net-(F1-Pad6)") (class "Default")
      (node (ref "F1") (pin "6") (pinfunction "6_6") (pintype "passive"))
      (node (ref "G1") (pin "2") (pinfunction "2_2") (pintype "passive"))
    )
    (net (code "84") (name "Net-(G1-Pad6)") (class "Default")
      (node (ref "G1") (pin "6") (pinfunction "6_6") (pintype "passive"))
      (node (ref "H1") (pin "2") (pinfunction "2_2") (pintype "passive"))
    )
    (net (code "85") (name "Net-(H1-Pad6)") (class "Default")
      (node (ref "H1") (pin "6") (pinfunction "6_6") (pintype "passive"))
      (node (ref "J2") (pin "2") (pinfunction "2_2") (pintype "passive"))
    )
    (net (code "86") (name "Net-(I1-Pad2)") (class "Default")
      (node (ref "I1") (pin "2") (pinfunction "2_2") (pintype "passive"))
      (node (ref "U2") (pin "6") (pinfunction "6_6") (pintype "passive"))
    )
    (net (code "87") (name "Net-(I1-Pad6)") (class "Default")
      (node (ref "I1") (pin "6") (pinfunction "6_6") (pintype "passive"))
      (node (ref "O1") (pin "2") (pinfunction "2_2") (pintype "passive"))
    )
    (net (code "88") (name "Net-(J2-Pad6)") (class "Default")
      (node (ref "J2") (pin "6") (pinfunction "6_6") (pintype "passive"))
      (node (ref "K1") (pin "2") (pinfunction "2_2") (pintype "passive"))
    )
    (net (code "89") (name "Net-(J3-Pad2)") (class "Default")
      (node (ref "J3") (pin "2") (pinfunction "2_2") (pintype "passive"))
      (node (ref "LCTRL1") (pin "2") (pinfunction "2_2") (pintype "passive"))
    )
    (net (code "90") (name "Net-(K1-Pad6)") (class "Default")
      (node (ref "K1") (pin "6") (pinfunction "6_6") (pintype "passive"))
      (node (ref "L1") (pin "2") (pinfunction "2_2") (pintype "passive"))
    )
    (net (code "91") (name "Net-(LALT1-Pad2)") (class "Default")
      (node (ref "LALT1") (pin "2") (pinfunction "2_2") (pintype "passive"))
      (node (ref "LGUI1") (pin "6") (pinfunction "6_6") (pintype "passive"))
    )
    (net (code "92") (name "Net-(LALT1-Pad6)") (class "Default")
      (node (ref "LALT1") (pin "6") (pinfunction "6_6") (pintype "passive"))
      (node (ref "SPACE1") (pin "2") (pinfunction "2_2") (pintype "passive"))
    )
    (net (code "93") (name "Net-(LCTRL1-Pad6)") (class "Default")
      (node (ref "LCTRL1") (pin "6") (pinfunction "6_6") (pintype "passive"))
      (node (ref "LGUI1") (pin "2") (pinfunction "2_2") (pintype "passive"))
    )
    (net (code "94") (name "Net-(LED1-K)") (class "Default")
      (node (ref "LED1") (pin "2") (pinfunction "K_2") (pintype "passive"))
      (node (ref "R7") (pin "2") (pinfunction "2_2") (pintype "passive"))
    )
    (net (code "95") (name "Net-(LSHIFT1-Pad2)") (class "Default")
      (node (ref "LSHIFT1") (pin "2") (pinfunction "2_2") (pintype "passive"))
      (node (ref "RIGHT1") (pin "6") (pinfunction "6_6") (pintype "passive"))
    )
    (net (code "96") (name "Net-(LSHIFT1-Pad6)") (class "Default")
      (node (ref "LSHIFT1") (pin "6") (pinfunction "6_6") (pintype "passive"))
      (node (ref "Z1") (pin "2") (pinfunction "2_2") (pintype "passive"))
    )
    (net (code "97") (name "Net-(M1-Pad2)") (class "Default")
      (node (ref "M1") (pin "2") (pinfunction "2_2") (pintype "passive"))
      (node (ref "N1") (pin "6") (pinfunction "6_6") (pintype "passive"))
    )
    (net (code "98") (name "Net-(M1-Pad6)") (class "Default")
      (node (ref "M1") (pin "6") (pinfunction "6_6") (pintype "passive"))
      (node (ref "TO1") (pin "2") (pinfunction "2_2") (pintype "passive"))
    )
    (net (code "99") (name "Net-(O1-Pad6)") (class "Default")
      (node (ref "O1") (pin "6") (pinfunction "6_6") (pintype "passive"))
      (node (ref "P1") (pin "2") (pinfunction "2_2") (pintype "passive"))
    )
    (net (code "100") (name "Net-(Q1-Pad6)") (class "Default")
      (node (ref "Q1") (pin "6") (pinfunction "6_6") (pintype "passive"))
      (node (ref "W1") (pin "2") (pinfunction "2_2") (pintype "passive"))
    )
    (net (code "101") (name "Net-(R6-Pad6)") (class "Default")
      (node (ref "R6") (pin "6") (pinfunction "6_6") (pintype "passive"))
      (node (ref "T1") (pin "2") (pinfunction "2_2") (pintype "passive"))
    )
    (net (code "102") (name "Net-(RSHIFT1-Pad2)") (class "Default")
      (node (ref "RSHIFT1") (pin "2") (pinfunction "2_2") (pintype "passive"))
      (node (ref "SPACE1") (pin "6") (pinfunction "6_6") (pintype "passive"))
    )
    (net (code "103") (name "Net-(T1-Pad6)") (class "Default")
      (node (ref "T1") (pin "6") (pinfunction "6_6") (pintype "passive"))
      (node (ref "Y1") (pin "2") (pinfunction "2_2") (pintype "passive"))
    )
    (net (code "104") (name "Net-(TO1-Pad6)") (class "Default")
      (node (ref "TO1") (pin "6") (pinfunction "6_6") (pintype "passive"))
      (node (ref "UP1") (pin "2") (pinfunction "2_2") (pintype "passive"))
    )
    (net (code "105") (name "Net-(U2-Pad2)") (class "Default")
      (node (ref "U2") (pin "2") (pinfunction "2_2") (pintype "passive"))
      (node (ref "Y1") (pin "6") (pinfunction "6_6") (pintype "passive"))
    )
    (net (code "106") (name "Net-(X2-Pad2)") (class "Default")
      (node (ref "X2") (pin "2") (pinfunction "2_2") (pintype "passive"))
      (node (ref "Z1") (pin "6") (pinfunction "6_6") (pintype "passive"))
    )
    (net (code "107") (name "VCC") (class "Default")
      (node (ref "A1") (pin "1") (pinfunction "1_1") (pintype "passive"))
      (node (ref "B1") (pin "1") (pinfunction "1_1") (pintype "passive"))
      (node (ref "BACKSPACE1") (pin "1") (pinfunction "1_1") (pintype "passive"))
      (node (ref "C9") (pin "1") (pinfunction "1_1") (pintype "passive"))
      (node (ref "CAPS1") (pin "1") (pinfunction "1_1") (pintype "passive"))
      (node (ref "D67") (pin "1") (pinfunction "1_1") (pintype "passive"))
      (node (ref "DEL1") (pin "1") (pinfunction "1_1") (pintype "passive"))
      (node (ref "DOWN1") (pin "1") (pinfunction "1_1") (pintype "passive"))
      (node (ref "E1") (pin "1") (pinfunction "1_1") (pintype "passive"))
      (node (ref "ENTER1") (pin "1") (pinfunction "1_1") (pintype "passive"))
      (node (ref "ESC1") (pin "1") (pinfunction "1_1") (pintype "passive"))
      (node (ref "F1") (pin "1") (pinfunction "1_1") (pintype "passive"))
      (node (ref "G1") (pin "1") (pinfunction "1_1") (pintype "passive"))
      (node (ref "H1") (pin "1") (pinfunction "1_1") (pintype "passive"))
      (node (ref "I1") (pin "1") (pinfunction "1_1") (pintype "passive"))
      (node (ref "J2") (pin "1") (pinfunction "1_1") (pintype "passive"))
      (node (ref "J3") (pin "3") (pinfunction "3_3") (pintype "passive"))
      (node (ref "K1") (pin "1") (pinfunction "1_1") (pintype "passive"))
      (node (ref "L1") (pin "1") (pinfunction "1_1") (pintype "passive"))
      (node (ref "LALT1") (pin "1") (pinfunction "1_1") (pintype "passive"))
      (node (ref "LCTRL1") (pin "1") (pinfunction "1_1") (pintype "passive"))
      (node (ref "LED1") (pin "1") (pinfunction "A_1") (pintype "passive"))
      (node (ref "LEFT1") (pin "1") (pinfunction "1_1") (pintype "passive"))
      (node (ref "LGUI1") (pin "1") (pinfunction "1_1") (pintype "passive"))
      (node (ref "LSHIFT1") (pin "1") (pinfunction "1_1") (pintype "passive"))
      (node (ref "M1") (pin "1") (pinfunction "1_1") (pintype "passive"))
      (node (ref "N1") (pin "1") (pinfunction "1_1") (pintype "passive"))
      (node (ref "O1") (pin "1") (pinfunction "1_1") (pintype "passive"))
      (node (ref "P1") (pin "1") (pinfunction "1_1") (pintype "passive"))
      (node (ref "Q1") (pin "1") (pinfunction "1_1") (pintype "passive"))
      (node (ref "R6") (pin "1") (pinfunction "1_1") (pintype "passive"))
      (node (ref "RIGHT1") (pin "1") (pinfunction "1_1") (pintype "passive"))
      (node (ref "RSHIFT1") (pin "1") (pinfunction "1_1") (pintype "passive"))
      (node (ref "S1") (pin "1") (pinfunction "1_1") (pintype "passive"))
      (node (ref "SPACE1") (pin "1") (pinfunction "1_1") (pintype "passive"))
      (node (ref "T1") (pin "1") (pinfunction "1_1") (pintype "passive"))
      (node (ref "TAB1") (pin "1") (pinfunction "1_1") (pintype "passive"))
      (node (ref "TO1") (pin "1") (pinfunction "1_1") (pintype "passive"))
      (node (ref "U2") (pin "1") (pinfunction "1_1") (pintype "passive"))
      (node (ref "UP1") (pin "1") (pinfunction "1_1") (pintype "passive"))
      (node (ref "V1") (pin "1") (pinfunction "1_1") (pintype "passive"))
      (node (ref "W1") (pin "1") (pinfunction "1_1") (pintype "passive"))
      (node (ref "X2") (pin "1") (pinfunction "1_1") (pintype "passive"))
      (node (ref "Y1") (pin "1") (pinfunction "1_1") (pintype "passive"))
      (node (ref "Z1") (pin "1") (pinfunction "1_1") (pintype "passive"))
    )
  )
)
